# M_GPIO_ADC.net
KiCad netlist of a schematic drawn in Altium Designer
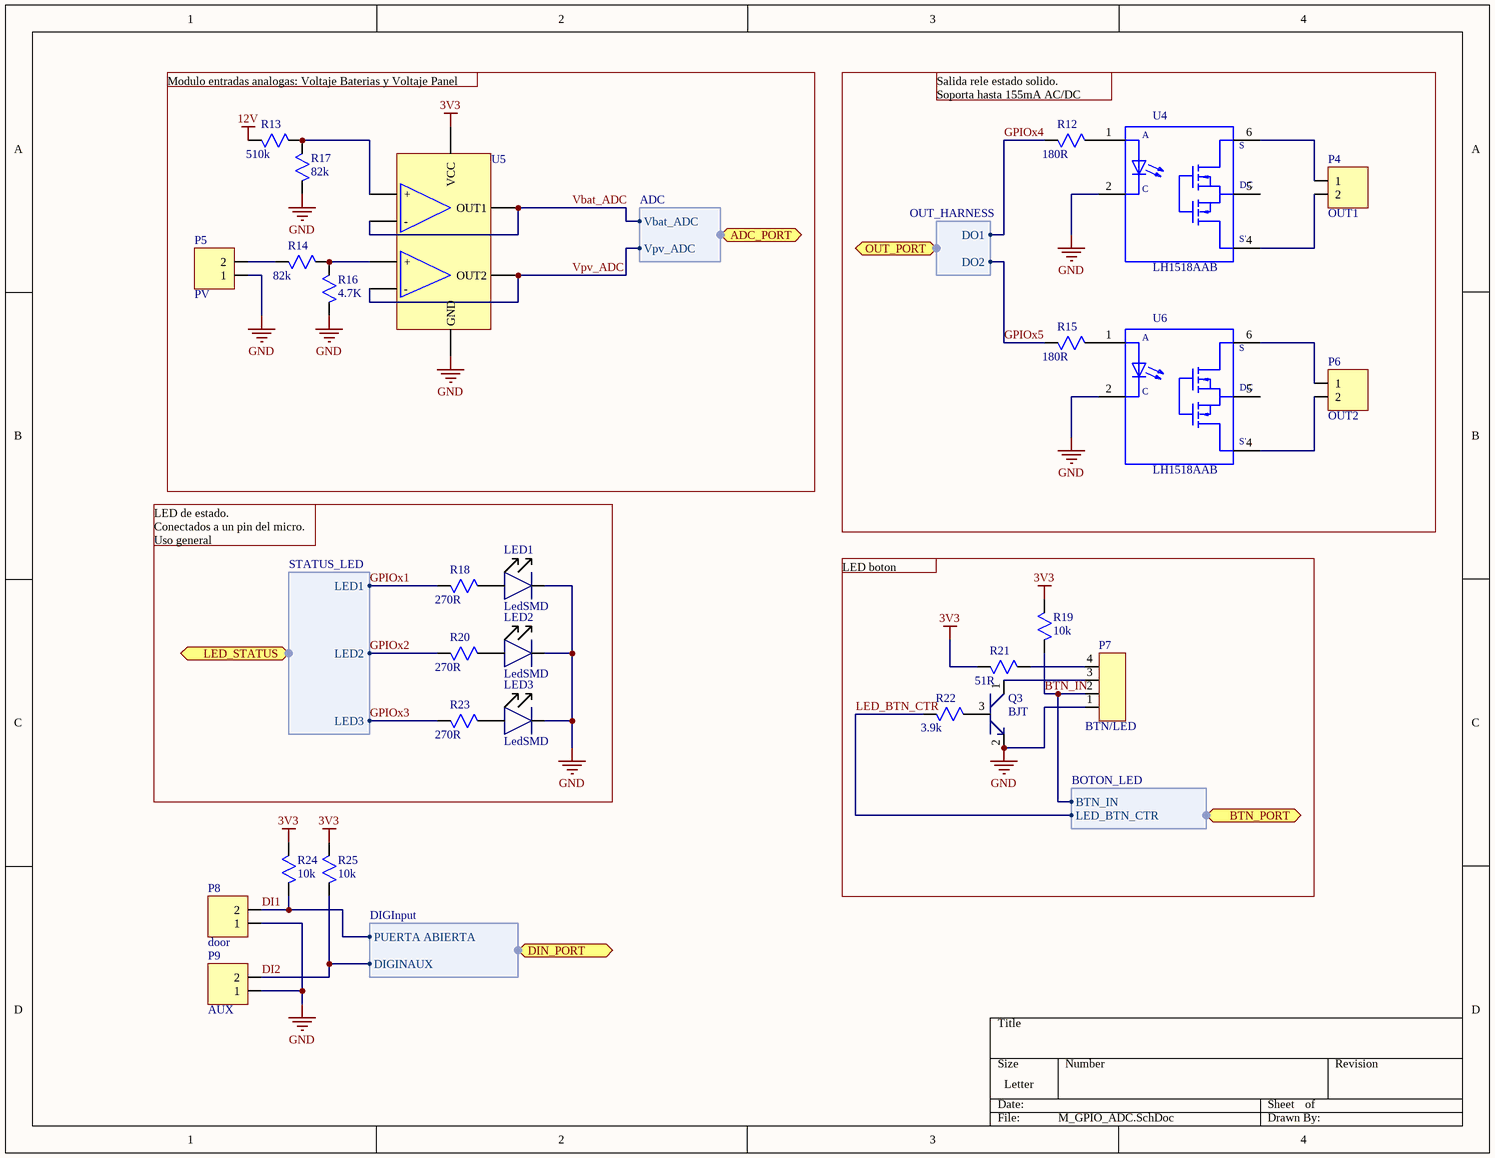
[diagram p0: M_GPIO_ADC.SchDoc]

(export (version "E")
  (design (tool "Eeschema 10.0.6"))
  (components
    (comp (ref "LED1")
      (value "LedSMD")
      (footprint "SMD1206")
      (description "Discrete Led SMD 1205 Green")
      (fields (field (name "DIGI-KEY PART NUMBER") "160-1169-1-ND") (field (name "PARTNO") "LTST-C150GKT"))
      (libsource (lib "PAT_Library") (part "LedSMD"))
    )
    (comp (ref "LED2")
      (value "LedSMD")
      (footprint "SMD1206")
      (description "Discrete Led SMD 1205 Green")
      (fields (field (name "DIGI-KEY PART NUMBER") "160-1169-1-ND") (field (name "PARTNO") "LTST-C150GKT"))
      (libsource (lib "PAT_Library") (part "LedSMD"))
    )
    (comp (ref "LED3")
      (value "LedSMD")
      (footprint "SMD1206")
      (description "Discrete Led SMD 1205 Green")
      (fields (field (name "DIGI-KEY PART NUMBER") "160-1169-1-ND") (field (name "PARTNO") "LTST-C150GKT"))
      (libsource (lib "PAT_Library") (part "LedSMD"))
    )
    (comp (ref "P4")
      (value "OUT1")
      (footprint "TBHDR2P3.5VERTICAL")
      (description "Connector 2 positions with pitch 3.5mm")
      (fields (field (name "DIGI-KEY PART NUMBER") "732-2763-ND") (field (name "PARTNO") "691321100002"))
      (libsource (lib "PAT Connectors Board") (part "TBHDR2P3.5"))
    )
    (comp (ref "P5")
      (value "PV")
      (footprint "TBHDR2P3.5VERTICAL")
      (description "Connector 2 positions with pitch 3.5mm")
      (fields (field (name "DIGI-KEY PART NUMBER") "732-2763-ND") (field (name "PARTNO") "691321100002"))
      (libsource (lib "") (part "TBHDR2P3.5_1"))
    )
    (comp (ref "P6")
      (value "OUT2")
      (footprint "TBHDR2P3.5VERTICAL")
      (description "Connector 2 positions with pitch 3.5mm")
      (fields (field (name "DIGI-KEY PART NUMBER") "732-2763-ND") (field (name "PARTNO") "691321100002"))
      (libsource (lib "PAT Connectors Board") (part "TBHDR2P3.5"))
    )
    (comp (ref "P7")
      (value "BTN/LED")
      (footprint "TBHDR4P3.5")
      (description "Connector 4 positions")
      (fields (field (name "DIGI-KEY PART NUMBER") "732-2765-ND") (field (name "PARTNO") "691321100004"))
      (libsource (lib "PAT Connectors Board") (part "TBHDR4P3.5"))
    )
    (comp (ref "P8")
      (value "door")
      (footprint "TBHDR2P3.5VERTICAL")
      (description "Connector 2 positions with pitch 3.5mm")
      (fields (field (name "DIGI-KEY PART NUMBER") "732-2763-ND") (field (name "PARTNO") "691321100002"))
      (libsource (lib "") (part "TBHDR2P3.5_1"))
    )
    (comp (ref "P9")
      (value "AUX")
      (footprint "TBHDR2P3.5VERTICAL")
      (description "Connector 2 positions with pitch 3.5mm")
      (fields (field (name "DIGI-KEY PART NUMBER") "732-2763-ND") (field (name "PARTNO") "691321100002"))
      (libsource (lib "") (part "TBHDR2P3.5_1"))
    )
    (comp (ref "Q3")
      (value "BJT")
      (footprint "BJT")
      (description "Transistor BJT")
      (fields
        (field (name "DIGI-KEY PART NUMBER") "MMBT2222A-FDICT-ND")
        (field (name "MANUFACTURERS PART NUMBER") "MMBT2222A-7-F")
      )
      (libsource (lib "PAT_Library") (part "BJT"))
    )
    (comp (ref "R12")
      (value "180R")
      (footprint "ResistorSMD0805")
      (description "Chip Resistor SMD")
      (fields
        (field (name "DIGI-KEY PART NUMBER") "311-180CRCT-ND")
        (field (name "MANUFACTURERS PART NUMBER") "RC0805FR-07180RL")
      )
      (libsource (lib "PAT_Library") (part "ResistorSMD"))
    )
    (comp (ref "R13")
      (value "510k")
      (footprint "ResistorSMD0805")
      (description "Chip Resistor SMD")
      (fields
        (field (name "DIGI-KEY PART NUMBER") "311-510KCRCT-ND")
        (field (name "PARTNO") "RC0805FR-07510KL")
      )
      (libsource (lib "PAT_Library") (part "ResistorSMD"))
    )
    (comp (ref "R14")
      (value "82k")
      (footprint "ResistorSMD0805")
      (description "Chip Resistor SMD")
      (fields
        (field (name "DIGI-KEY PART NUMBER") "311-82.0KCRCT-ND")
        (field (name "PARTNO") "RC0805FR-0782KL")
      )
      (libsource (lib "PAT_Library") (part "ResistorSMD"))
    )
    (comp (ref "R15")
      (value "180R")
      (footprint "ResistorSMD0805")
      (description "Chip Resistor SMD")
      (fields
        (field (name "DIGI-KEY PART NUMBER") "311-180CRCT-ND")
        (field (name "MANUFACTURERS PART NUMBER") "RC0805FR-07180RL")
      )
      (libsource (lib "PAT_Library") (part "ResistorSMD"))
    )
    (comp (ref "R16")
      (value "4.7K")
      (footprint "ResistorSMD0805")
      (description "Chip Resistor SMD")
      (fields (field (name "DIGI-KEY PART NUMBER") "P4.7KACT-ND") (field (name "PARTNO") "ERJ-6GEYJ472V"))
      (libsource (lib "PAT_Library") (part "ResistorSMD"))
    )
    (comp (ref "R17")
      (value "82k")
      (footprint "ResistorSMD0805")
      (description "Chip Resistor SMD")
      (fields
        (field (name "DIGI-KEY PART NUMBER") "311-82.0KCRCT-ND")
        (field (name "PARTNO") "RC0805FR-0782KL")
      )
      (libsource (lib "PAT_Library") (part "ResistorSMD"))
    )
    (comp (ref "R18")
      (value "270R")
      (footprint "ResistorSMD0805")
      (description "Chip Resistor SMD")
      (fields
        (field (name "DIGI-KEY PART NUMBER") "P270CCT-ND")
        (field (name "MANUFACTURERS PART NUMBER") "ERJ-6ENF2700V")
      )
      (libsource (lib "PAT_Library") (part "ResistorSMD"))
    )
    (comp (ref "R19")
      (value "10k")
      (footprint "ResistorSMD0805")
      (description "Chip Resistor SMD")
      (fields
        (field (name "DIGI-KEY PART NUMBER") "311-10.0KCRCT-ND")
        (field (name "MANUFACTURERS PART NUMBER") "RC0805FR-0710KL")
      )
      (libsource (lib "PAT_Library") (part "ResistorSMD"))
    )
    (comp (ref "R20")
      (value "270R")
      (footprint "ResistorSMD0805")
      (description "Chip Resistor SMD")
      (fields
        (field (name "DIGI-KEY PART NUMBER") "P270CCT-ND")
        (field (name "MANUFACTURERS PART NUMBER") "ERJ-6ENF2700V")
      )
      (libsource (lib "PAT_Library") (part "ResistorSMD"))
    )
    (comp (ref "R21")
      (value "51R")
      (footprint "ResistorSMD0805")
      (description "Chip Resistor SMD")
      (fields
        (field (name "DIGI-KEY PART NUMBER") "CRM0805-FX-51R0ELFCT-ND")
        (field (name "MANUFACTURERS PART NUMBER") "CRM0805-FX-51R0ELF")
      )
      (libsource (lib "PAT_Library") (part "ResistorSMD"))
    )
    (comp (ref "R22")
      (value "3.9k")
      (footprint "ResistorSMD0805")
      (description "Chip Resistor SMD")
      (fields
        (field (name "DIGI-KEY PART NUMBER") "311-3.90KHRCT-ND")
        (field (name "MANUFACTURERS PART NUMBER") "RC0603FR-073K9L")
      )
      (libsource (lib "PAT_Library") (part "ResistorSMD"))
    )
    (comp (ref "R23")
      (value "270R")
      (footprint "ResistorSMD0805")
      (description "Chip Resistor SMD")
      (fields
        (field (name "DIGI-KEY PART NUMBER") "P270CCT-ND")
        (field (name "MANUFACTURERS PART NUMBER") "ERJ-6ENF2700V")
      )
      (libsource (lib "PAT_Library") (part "ResistorSMD"))
    )
    (comp (ref "R24")
      (value "10k")
      (footprint "ResistorSMD0805")
      (description "Chip Resistor SMD")
      (fields
        (field (name "DIGI-KEY PART NUMBER") "311-10.0KCRCT-ND")
        (field (name "MANUFACTURERS PART NUMBER") "RC0805FR-0710KL")
      )
      (libsource (lib "PAT_Library") (part "ResistorSMD"))
    )
    (comp (ref "R25")
      (value "10k")
      (footprint "ResistorSMD0805")
      (description "Chip Resistor SMD")
      (fields
        (field (name "DIGI-KEY PART NUMBER") "311-10.0KCRCT-ND")
        (field (name "MANUFACTURERS PART NUMBER") "RC0805FR-0710KL")
      )
      (libsource (lib "PAT_Library") (part "ResistorSMD"))
    )
    (comp (ref "U4")
      (value "LH1518AAB")
      (footprint "SOIC254P1005X390-6N")
      (description "LH1518AAB Series SPST _1 Form A_ Solid State Relay Surface Mount - SMD-6")
      (fields (field (name "DIGI-KEY PART NUMBER") "LH1518AAB-ND"))
      (libsource (lib "LH1518AAB") (part "LH1518AAB"))
    )
    (comp (ref "U5")
      (value "Operacional")
      (footprint "SO8")
      (description "2channel Vcc=4-16Vmax")
      (fields (field (name "DIGI-KEY PART NUMBER") "497-1591-1-ND") (field (name "PARTNO") "LM358DT"))
      (libsource (lib "PAT_Library") (part "Operacional"))
    )
    (comp (ref "U6")
      (value "LH1518AAB")
      (footprint "SOIC254P1005X390-6N")
      (description "LH1518AAB Series SPST _1 Form A_ Solid State Relay Surface Mount - SMD-6")
      (fields (field (name "DIGI-KEY PART NUMBER") "LH1518AAB-ND"))
      (libsource (lib "LH1518AAB") (part "LH1518AAB"))
    )
  )
  (nets
    (net (code "6") (name "/BTN_IN") (class "Default")
      (node (ref "P7") (pin "2") (pinfunction "2_2") (pintype "passive"))
      (node (ref "R19") (pin "1") (pinfunction "1_1") (pintype "passive"))
    )
    (net (code "7") (name "/DI1") (class "Default")
      (node (ref "P8") (pin "2") (pinfunction "2_2") (pintype "passive"))
      (node (ref "R24") (pin "1") (pinfunction "1_1") (pintype "passive"))
    )
    (net (code "8") (name "/DI2") (class "Default")
      (node (ref "P9") (pin "2") (pinfunction "2_2") (pintype "passive"))
      (node (ref "R25") (pin "1") (pinfunction "1_1") (pintype "passive"))
    )
    (net (code "9") (name "/GPIOx1") (class "Default")
      (node (ref "R18") (pin "1") (pinfunction "1_1") (pintype "passive"))
    )
    (net (code "10") (name "/GPIOx2") (class "Default")
      (node (ref "R20") (pin "1") (pinfunction "1_1") (pintype "passive"))
    )
    (net (code "11") (name "/GPIOx3") (class "Default")
      (node (ref "R23") (pin "1") (pinfunction "1_1") (pintype "passive"))
    )
    (net (code "12") (name "/GPIOx4") (class "Default")
      (node (ref "R12") (pin "1") (pinfunction "1_1") (pintype "passive"))
    )
    (net (code "13") (name "/GPIOx5") (class "Default")
      (node (ref "R15") (pin "1") (pinfunction "1_1") (pintype "passive"))
    )
    (net (code "14") (name "/LED_BTN_CTR") (class "Default")
      (node (ref "R22") (pin "1") (pinfunction "1_1") (pintype "passive"))
    )
    (net (code "15") (name "/Vbat_ADC") (class "Default")
      (node (ref "U5") (pin "1") (pinfunction "OUT1_1") (pintype "passive"))
      (node (ref "U5") (pin "2") (pinfunction "-_2") (pintype "passive"))
    )
    (net (code "16") (name "/Vpv_ADC") (class "Default")
      (node (ref "U5") (pin "6") (pinfunction "-_6") (pintype "passive"))
      (node (ref "U5") (pin "7") (pinfunction "OUT2_7") (pintype "passive"))
    )
    (net (code "22") (name "3V3") (class "Default")
      (node (ref "R19") (pin "2") (pinfunction "2_2") (pintype "passive"))
      (node (ref "R21") (pin "1") (pinfunction "1_1") (pintype "passive"))
      (node (ref "R24") (pin "2") (pinfunction "2_2") (pintype "passive"))
      (node (ref "R25") (pin "2") (pinfunction "2_2") (pintype "passive"))
      (node (ref "U5") (pin "8") (pinfunction "VCC_8") (pintype "passive"))
    )
    (net (code "23") (name "12V") (class "Default")
      (node (ref "R13") (pin "1") (pinfunction "1_1") (pintype "passive"))
    )
    (net (code "24") (name "GND") (class "Default")
      (node (ref "LED1") (pin "1") (pinfunction "1_1") (pintype "passive"))
      (node (ref "LED2") (pin "1") (pinfunction "1_1") (pintype "passive"))
      (node (ref "LED3") (pin "1") (pinfunction "1_1") (pintype "passive"))
      (node (ref "P5") (pin "1") (pinfunction "1_1") (pintype "passive"))
      (node (ref "P7") (pin "1") (pinfunction "1_1") (pintype "passive"))
      (node (ref "P8") (pin "1") (pinfunction "1_1") (pintype "passive"))
      (node (ref "P9") (pin "1") (pinfunction "1_1") (pintype "passive"))
      (node (ref "Q3") (pin "2") (pinfunction "2_2") (pintype "passive"))
      (node (ref "R16") (pin "1") (pinfunction "1_1") (pintype "passive"))
      (node (ref "R17") (pin "1") (pinfunction "1_1") (pintype "passive"))
      (node (ref "U4") (pin "2") (pinfunction "C_2") (pintype "passive"))
      (node (ref "U5") (pin "4") (pinfunction "GND_4") (pintype "passive"))
      (node (ref "U6") (pin "2") (pinfunction "C_2") (pintype "passive"))
    )
    (net (code "25") (name "Net-(LED1-Pad2)") (class "Default")
      (node (ref "LED1") (pin "2") (pinfunction "2_2") (pintype "passive"))
      (node (ref "R18") (pin "2") (pinfunction "2_2") (pintype "passive"))
    )
    (net (code "26") (name "Net-(LED2-Pad2)") (class "Default")
      (node (ref "LED2") (pin "2") (pinfunction "2_2") (pintype "passive"))
      (node (ref "R20") (pin "2") (pinfunction "2_2") (pintype "passive"))
    )
    (net (code "27") (name "Net-(LED3-Pad2)") (class "Default")
      (node (ref "LED3") (pin "2") (pinfunction "2_2") (pintype "passive"))
      (node (ref "R23") (pin "2") (pinfunction "2_2") (pintype "passive"))
    )
    (net (code "28") (name "Net-(P5-Pad2)") (class "Default")
      (node (ref "P5") (pin "2") (pinfunction "2_2") (pintype "passive"))
      (node (ref "R14") (pin "1") (pinfunction "1_1") (pintype "passive"))
    )
    (net (code "29") (name "Net-(P7-Pad3)") (class "Default")
      (node (ref "P7") (pin "3") (pinfunction "3_3") (pintype "passive"))
      (node (ref "Q3") (pin "1") (pinfunction "1_1") (pintype "passive"))
    )
    (net (code "30") (name "Net-(P7-Pad4)") (class "Default")
      (node (ref "P7") (pin "4") (pinfunction "4_4") (pintype "passive"))
      (node (ref "R21") (pin "2") (pinfunction "2_2") (pintype "passive"))
    )
    (net (code "31") (name "Net-(Q3-Pad3)") (class "Default")
      (node (ref "Q3") (pin "3") (pinfunction "3_3") (pintype "passive"))
      (node (ref "R22") (pin "2") (pinfunction "2_2") (pintype "passive"))
    )
    (net (code "32") (name "Net-(R13-Pad2)") (class "Default")
      (node (ref "R13") (pin "2") (pinfunction "2_2") (pintype "passive"))
      (node (ref "R17") (pin "2") (pinfunction "2_2") (pintype "passive"))
      (node (ref "U5") (pin "3") (pinfunction "+_3") (pintype "passive"))
    )
    (net (code "33") (name "Net-(R14-Pad2)") (class "Default")
      (node (ref "R14") (pin "2") (pinfunction "2_2") (pintype "passive"))
      (node (ref "R16") (pin "2") (pinfunction "2_2") (pintype "passive"))
      (node (ref "U5") (pin "5") (pinfunction "+_5") (pintype "passive"))
    )
    (net (code "34") (name "Net-(U4-A)") (class "Default")
      (node (ref "R12") (pin "2") (pinfunction "2_2") (pintype "passive"))
      (node (ref "U4") (pin "1") (pinfunction "A_1") (pintype "passive"))
    )
    (net (code "35") (name "Net-(U4-S')") (class "Default")
      (node (ref "P4") (pin "2") (pinfunction "2_2") (pintype "passive"))
      (node (ref "U4") (pin "4") (pinfunction "S'_4") (pintype "passive"))
    )
    (net (code "36") (name "Net-(U4-S)") (class "Default")
      (node (ref "P4") (pin "1") (pinfunction "1_1") (pintype "passive"))
      (node (ref "U4") (pin "6") (pinfunction "S_6") (pintype "passive"))
    )
    (net (code "37") (name "Net-(U6-A)") (class "Default")
      (node (ref "R15") (pin "2") (pinfunction "2_2") (pintype "passive"))
      (node (ref "U6") (pin "1") (pinfunction "A_1") (pintype "passive"))
    )
    (net (code "38") (name "Net-(U6-S')") (class "Default")
      (node (ref "P6") (pin "2") (pinfunction "2_2") (pintype "passive"))
      (node (ref "U6") (pin "4") (pinfunction "S'_4") (pintype "passive"))
    )
    (net (code "39") (name "Net-(U6-S)") (class "Default")
      (node (ref "P6") (pin "1") (pinfunction "1_1") (pintype "passive"))
      (node (ref "U6") (pin "6") (pinfunction "S_6") (pintype "passive"))
    )
    (net (code "40") (name "unconnected-(U4-DC-Pad5)") (class "Default")
      (node (ref "U4") (pin "5") (pinfunction "DC_5") (pintype "passive"))
    )
    (net (code "41") (name "unconnected-(U6-DC-Pad5)") (class "Default")
      (node (ref "U6") (pin "5") (pinfunction "DC_5") (pintype "passive"))
    )
  )
)
